# 03_-_MATRIX_SCHEMATIC.net
KiCad netlist of a schematic drawn in Altium Designer
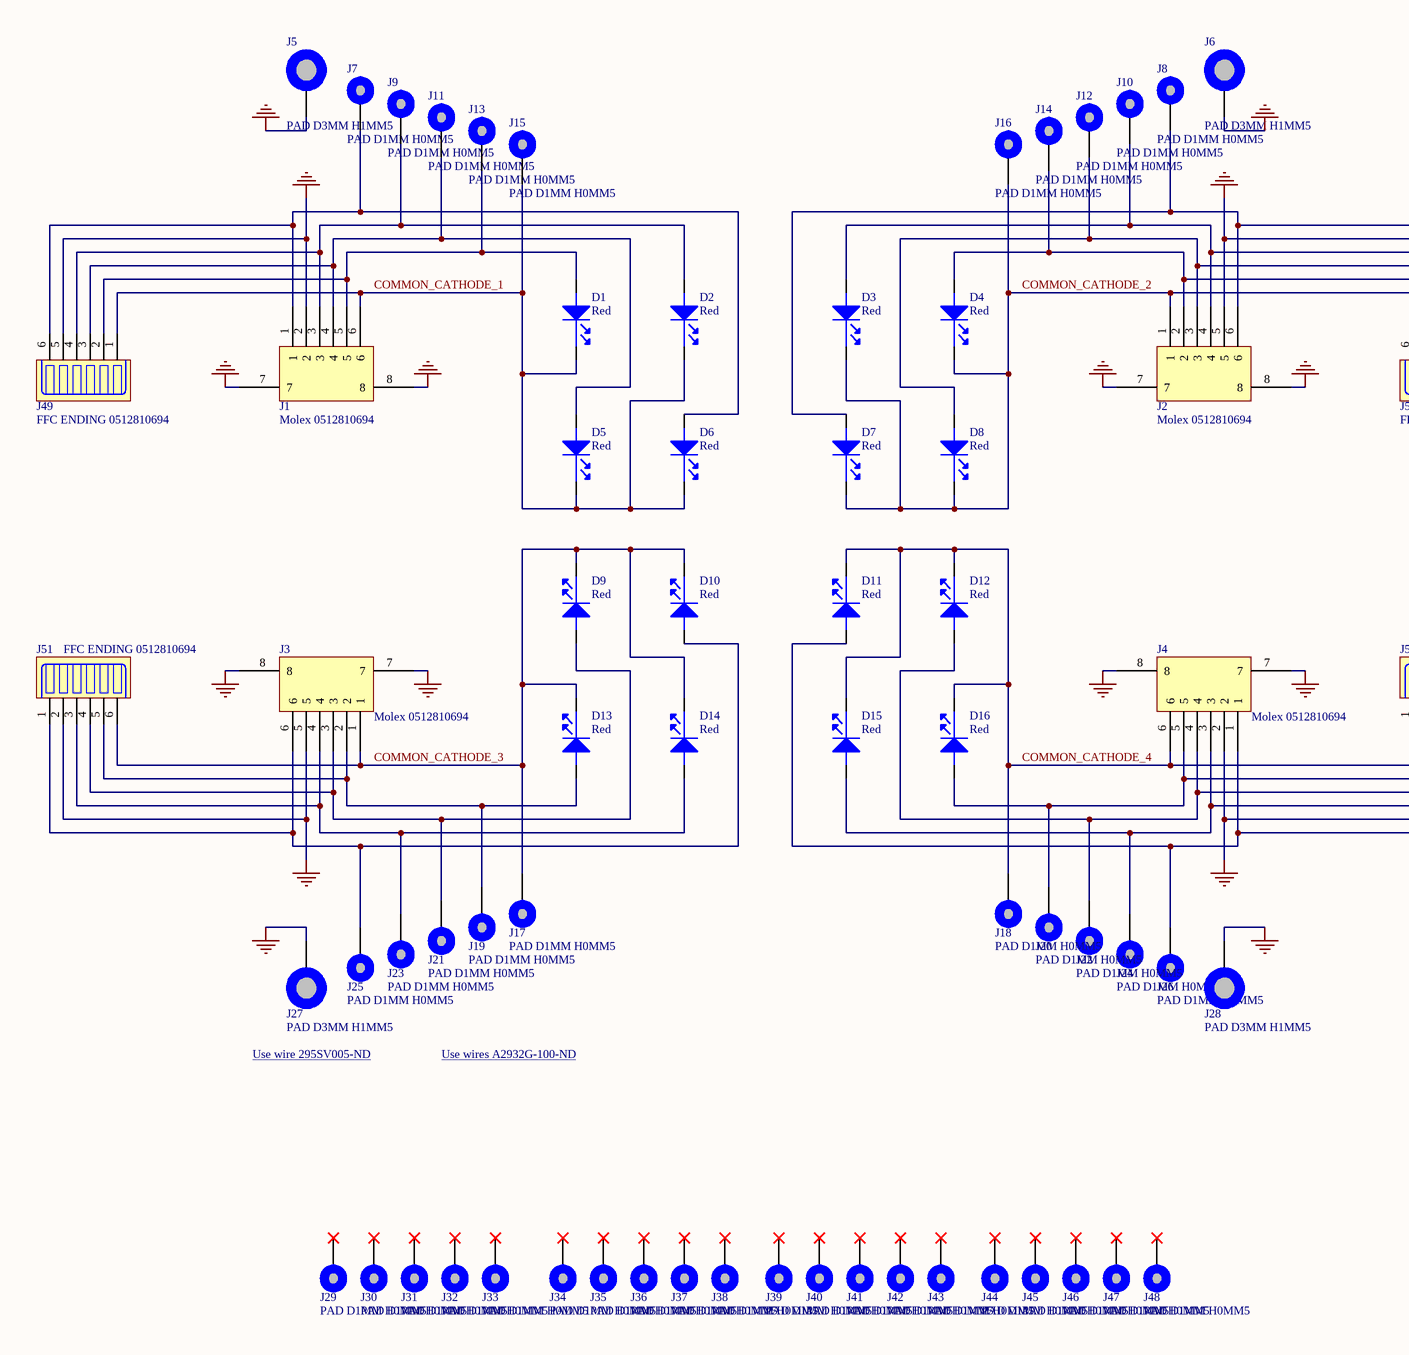
[diagram p0: [03] - MATRIX SCHEMATIC.SchDoc, left]
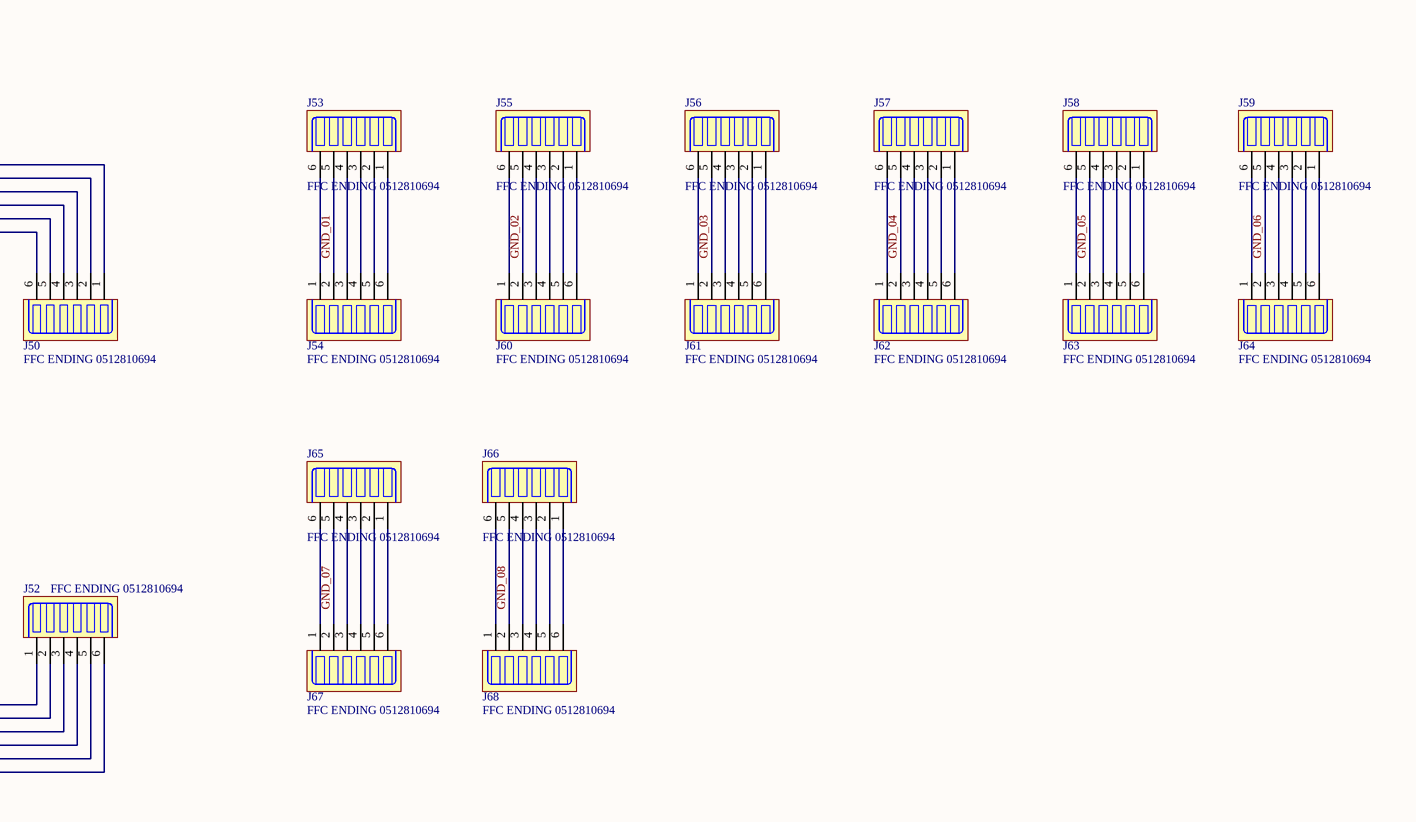
[diagram p1: [03] - MATRIX SCHEMATIC.SchDoc, right]

(export (version "E")
  (design (tool "Eeschema 10.0.6"))
  (components
    (comp (ref "D1")
      (value "Red")
      (footprint "LED_0603")
      (description "LED SMARTLED RED 630NM 0603 SMD")
      (fields
        (field (name "MANUFACTURER") "OSRAM Opto Semiconductors Inc")
        (field (name "MANUFACTURER PART NUMBER") "LS L29K-H1J2-1-Z")
      )
      (libsource (lib "Integrated_Library_FEDEVEL_APR_2015") (part "LS L29K-H1J2-1-Z"))
    )
    (comp (ref "D2")
      (value "Red")
      (footprint "LED_0603")
      (description "LED SMARTLED RED 630NM 0603 SMD")
      (fields
        (field (name "MANUFACTURER") "OSRAM Opto Semiconductors Inc")
        (field (name "MANUFACTURER PART NUMBER") "LS L29K-H1J2-1-Z")
      )
      (libsource (lib "Integrated_Library_FEDEVEL_APR_2015") (part "LS L29K-H1J2-1-Z"))
    )
    (comp (ref "D3")
      (value "Red")
      (footprint "LED_0603")
      (description "LED SMARTLED RED 630NM 0603 SMD")
      (fields
        (field (name "MANUFACTURER") "OSRAM Opto Semiconductors Inc")
        (field (name "MANUFACTURER PART NUMBER") "LS L29K-H1J2-1-Z")
      )
      (libsource (lib "Integrated_Library_FEDEVEL_APR_2015") (part "LS L29K-H1J2-1-Z"))
    )
    (comp (ref "D4")
      (value "Red")
      (footprint "LED_0603")
      (description "LED SMARTLED RED 630NM 0603 SMD")
      (fields
        (field (name "MANUFACTURER") "OSRAM Opto Semiconductors Inc")
        (field (name "MANUFACTURER PART NUMBER") "LS L29K-H1J2-1-Z")
      )
      (libsource (lib "Integrated_Library_FEDEVEL_APR_2015") (part "LS L29K-H1J2-1-Z"))
    )
    (comp (ref "D5")
      (value "Red")
      (footprint "LED_0603")
      (description "LED SMARTLED RED 630NM 0603 SMD")
      (fields
        (field (name "MANUFACTURER") "OSRAM Opto Semiconductors Inc")
        (field (name "MANUFACTURER PART NUMBER") "LS L29K-H1J2-1-Z")
      )
      (libsource (lib "Integrated_Library_FEDEVEL_APR_2015") (part "LS L29K-H1J2-1-Z"))
    )
    (comp (ref "D6")
      (value "Red")
      (footprint "LED_0603")
      (description "LED SMARTLED RED 630NM 0603 SMD")
      (fields
        (field (name "MANUFACTURER") "OSRAM Opto Semiconductors Inc")
        (field (name "MANUFACTURER PART NUMBER") "LS L29K-H1J2-1-Z")
      )
      (libsource (lib "Integrated_Library_FEDEVEL_APR_2015") (part "LS L29K-H1J2-1-Z"))
    )
    (comp (ref "D7")
      (value "Red")
      (footprint "LED_0603")
      (description "LED SMARTLED RED 630NM 0603 SMD")
      (fields
        (field (name "MANUFACTURER") "OSRAM Opto Semiconductors Inc")
        (field (name "MANUFACTURER PART NUMBER") "LS L29K-H1J2-1-Z")
      )
      (libsource (lib "Integrated_Library_FEDEVEL_APR_2015") (part "LS L29K-H1J2-1-Z"))
    )
    (comp (ref "D8")
      (value "Red")
      (footprint "LED_0603")
      (description "LED SMARTLED RED 630NM 0603 SMD")
      (fields
        (field (name "MANUFACTURER") "OSRAM Opto Semiconductors Inc")
        (field (name "MANUFACTURER PART NUMBER") "LS L29K-H1J2-1-Z")
      )
      (libsource (lib "Integrated_Library_FEDEVEL_APR_2015") (part "LS L29K-H1J2-1-Z"))
    )
    (comp (ref "D9")
      (value "Red")
      (footprint "LED_0603")
      (description "LED SMARTLED RED 630NM 0603 SMD")
      (fields
        (field (name "MANUFACTURER") "OSRAM Opto Semiconductors Inc")
        (field (name "MANUFACTURER PART NUMBER") "LS L29K-H1J2-1-Z")
      )
      (libsource (lib "Integrated_Library_FEDEVEL_APR_2015") (part "LS L29K-H1J2-1-Z"))
    )
    (comp (ref "D10")
      (value "Red")
      (footprint "LED_0603")
      (description "LED SMARTLED RED 630NM 0603 SMD")
      (fields
        (field (name "MANUFACTURER") "OSRAM Opto Semiconductors Inc")
        (field (name "MANUFACTURER PART NUMBER") "LS L29K-H1J2-1-Z")
      )
      (libsource (lib "Integrated_Library_FEDEVEL_APR_2015") (part "LS L29K-H1J2-1-Z"))
    )
    (comp (ref "D11")
      (value "Red")
      (footprint "LED_0603")
      (description "LED SMARTLED RED 630NM 0603 SMD")
      (fields
        (field (name "MANUFACTURER") "OSRAM Opto Semiconductors Inc")
        (field (name "MANUFACTURER PART NUMBER") "LS L29K-H1J2-1-Z")
      )
      (libsource (lib "Integrated_Library_FEDEVEL_APR_2015") (part "LS L29K-H1J2-1-Z"))
    )
    (comp (ref "D12")
      (value "Red")
      (footprint "LED_0603")
      (description "LED SMARTLED RED 630NM 0603 SMD")
      (fields
        (field (name "MANUFACTURER") "OSRAM Opto Semiconductors Inc")
        (field (name "MANUFACTURER PART NUMBER") "LS L29K-H1J2-1-Z")
      )
      (libsource (lib "Integrated_Library_FEDEVEL_APR_2015") (part "LS L29K-H1J2-1-Z"))
    )
    (comp (ref "D13")
      (value "Red")
      (footprint "LED_0603")
      (description "LED SMARTLED RED 630NM 0603 SMD")
      (fields
        (field (name "MANUFACTURER") "OSRAM Opto Semiconductors Inc")
        (field (name "MANUFACTURER PART NUMBER") "LS L29K-H1J2-1-Z")
      )
      (libsource (lib "Integrated_Library_FEDEVEL_APR_2015") (part "LS L29K-H1J2-1-Z"))
    )
    (comp (ref "D14")
      (value "Red")
      (footprint "LED_0603")
      (description "LED SMARTLED RED 630NM 0603 SMD")
      (fields
        (field (name "MANUFACTURER") "OSRAM Opto Semiconductors Inc")
        (field (name "MANUFACTURER PART NUMBER") "LS L29K-H1J2-1-Z")
      )
      (libsource (lib "Integrated_Library_FEDEVEL_APR_2015") (part "LS L29K-H1J2-1-Z"))
    )
    (comp (ref "D15")
      (value "Red")
      (footprint "LED_0603")
      (description "LED SMARTLED RED 630NM 0603 SMD")
      (fields
        (field (name "MANUFACTURER") "OSRAM Opto Semiconductors Inc")
        (field (name "MANUFACTURER PART NUMBER") "LS L29K-H1J2-1-Z")
      )
      (libsource (lib "Integrated_Library_FEDEVEL_APR_2015") (part "LS L29K-H1J2-1-Z"))
    )
    (comp (ref "D16")
      (value "Red")
      (footprint "LED_0603")
      (description "LED SMARTLED RED 630NM 0603 SMD")
      (fields
        (field (name "MANUFACTURER") "OSRAM Opto Semiconductors Inc")
        (field (name "MANUFACTURER PART NUMBER") "LS L29K-H1J2-1-Z")
      )
      (libsource (lib "Integrated_Library_FEDEVEL_APR_2015") (part "LS L29K-H1J2-1-Z"))
    )
    (comp (ref "J1")
      (value "Molex 0512810694")
      (footprint "0512810694")
      (description "Conn FPC Connector SKT 6 POS 0.5mm Solder RA SMD Easy-On™ Embossed T/R")
      (fields
        (field (name "MANUFACTURER") "Molex")
        (field (name "MANUFACTURER PART NUMBER") "0512810694")
        (field (name ".CREATOR") "RF")
      )
      (libsource (lib "") (part "0512810694_1"))
    )
    (comp (ref "J2")
      (value "Molex 0512810694")
      (footprint "0512810694")
      (description "Conn FPC Connector SKT 6 POS 0.5mm Solder RA SMD Easy-On™ Embossed T/R")
      (fields
        (field (name "MANUFACTURER") "Molex")
        (field (name "MANUFACTURER PART NUMBER") "0512810694")
        (field (name ".CREATOR") "RF")
      )
      (libsource (lib "") (part "0512810694_1"))
    )
    (comp (ref "J3")
      (value "Molex 0512810694")
      (footprint "0512810694")
      (description "Conn FPC Connector SKT 6 POS 0.5mm Solder RA SMD Easy-On™ Embossed T/R")
      (fields
        (field (name "MANUFACTURER") "Molex")
        (field (name "MANUFACTURER PART NUMBER") "0512810694")
        (field (name ".CREATOR") "RF")
      )
      (libsource (lib "FlexCube_Matrix_4x4 Schlib") (part "0512810694"))
    )
    (comp (ref "J4")
      (value "Molex 0512810694")
      (footprint "0512810694")
      (description "Conn FPC Connector SKT 6 POS 0.5mm Solder RA SMD Easy-On™ Embossed T/R")
      (fields
        (field (name "MANUFACTURER") "Molex")
        (field (name "MANUFACTURER PART NUMBER") "0512810694")
        (field (name ".CREATOR") "RF")
      )
      (libsource (lib "FlexCube_Matrix_4x4 Schlib") (part "0512810694"))
    )
    (comp (ref "J5")
      (value "PAD D3MM H1MM5")
      (footprint "PAD_D3MM_H1MM5")
      (libsource (lib "FlexCube_Matrix_4x4 Schlib") (part "PAD D3MM H1MM5"))
    )
    (comp (ref "J6")
      (value "PAD D3MM H1MM5")
      (footprint "PAD_D3MM_H1MM5")
      (libsource (lib "FlexCube_Matrix_4x4 Schlib") (part "PAD D3MM H1MM5"))
    )
    (comp (ref "J7")
      (value "PAD D1MM H0MM5")
      (footprint "PAD_D1MM_H0MM5")
      (libsource (lib "FlexCube_Matrix_4x4 Schlib") (part "PAD D1MM H0MM5"))
    )
    (comp (ref "J8")
      (value "PAD D1MM H0MM5")
      (footprint "PAD_D1MM_H0MM5")
      (libsource (lib "FlexCube_Matrix_4x4 Schlib") (part "PAD D1MM H0MM5"))
    )
    (comp (ref "J9")
      (value "PAD D1MM H0MM5")
      (footprint "PAD_D1MM_H0MM5")
      (libsource (lib "FlexCube_Matrix_4x4 Schlib") (part "PAD D1MM H0MM5"))
    )
    (comp (ref "J10")
      (value "PAD D1MM H0MM5")
      (footprint "PAD_D1MM_H0MM5")
      (libsource (lib "FlexCube_Matrix_4x4 Schlib") (part "PAD D1MM H0MM5"))
    )
    (comp (ref "J11")
      (value "PAD D1MM H0MM5")
      (footprint "PAD_D1MM_H0MM5")
      (libsource (lib "FlexCube_Matrix_4x4 Schlib") (part "PAD D1MM H0MM5"))
    )
    (comp (ref "J12")
      (value "PAD D1MM H0MM5")
      (footprint "PAD_D1MM_H0MM5")
      (libsource (lib "FlexCube_Matrix_4x4 Schlib") (part "PAD D1MM H0MM5"))
    )
    (comp (ref "J13")
      (value "PAD D1MM H0MM5")
      (footprint "PAD_D1MM_H0MM5")
      (libsource (lib "FlexCube_Matrix_4x4 Schlib") (part "PAD D1MM H0MM5"))
    )
    (comp (ref "J14")
      (value "PAD D1MM H0MM5")
      (footprint "PAD_D1MM_H0MM5")
      (libsource (lib "FlexCube_Matrix_4x4 Schlib") (part "PAD D1MM H0MM5"))
    )
    (comp (ref "J15")
      (value "PAD D1MM H0MM5")
      (footprint "PAD_D1MM_H0MM5")
      (libsource (lib "FlexCube_Matrix_4x4 Schlib") (part "PAD D1MM H0MM5"))
    )
    (comp (ref "J16")
      (value "PAD D1MM H0MM5")
      (footprint "PAD_D1MM_H0MM5")
      (libsource (lib "FlexCube_Matrix_4x4 Schlib") (part "PAD D1MM H0MM5"))
    )
    (comp (ref "J17")
      (value "PAD D1MM H0MM5")
      (footprint "PAD_D1MM_H0MM5")
      (libsource (lib "FlexCube_Matrix_4x4 Schlib") (part "PAD D1MM H0MM5"))
    )
    (comp (ref "J18")
      (value "PAD D1MM H0MM5")
      (footprint "PAD_D1MM_H0MM5")
      (libsource (lib "FlexCube_Matrix_4x4 Schlib") (part "PAD D1MM H0MM5"))
    )
    (comp (ref "J19")
      (value "PAD D1MM H0MM5")
      (footprint "PAD_D1MM_H0MM5")
      (libsource (lib "FlexCube_Matrix_4x4 Schlib") (part "PAD D1MM H0MM5"))
    )
    (comp (ref "J20")
      (value "PAD D1MM H0MM5")
      (footprint "PAD_D1MM_H0MM5")
      (libsource (lib "FlexCube_Matrix_4x4 Schlib") (part "PAD D1MM H0MM5"))
    )
    (comp (ref "J21")
      (value "PAD D1MM H0MM5")
      (footprint "PAD_D1MM_H0MM5")
      (libsource (lib "FlexCube_Matrix_4x4 Schlib") (part "PAD D1MM H0MM5"))
    )
    (comp (ref "J22")
      (value "PAD D1MM H0MM5")
      (footprint "PAD_D1MM_H0MM5")
      (libsource (lib "FlexCube_Matrix_4x4 Schlib") (part "PAD D1MM H0MM5"))
    )
    (comp (ref "J23")
      (value "PAD D1MM H0MM5")
      (footprint "PAD_D1MM_H0MM5")
      (libsource (lib "FlexCube_Matrix_4x4 Schlib") (part "PAD D1MM H0MM5"))
    )
    (comp (ref "J24")
      (value "PAD D1MM H0MM5")
      (footprint "PAD_D1MM_H0MM5")
      (libsource (lib "FlexCube_Matrix_4x4 Schlib") (part "PAD D1MM H0MM5"))
    )
    (comp (ref "J25")
      (value "PAD D1MM H0MM5")
      (footprint "PAD_D1MM_H0MM5")
      (libsource (lib "FlexCube_Matrix_4x4 Schlib") (part "PAD D1MM H0MM5"))
    )
    (comp (ref "J26")
      (value "PAD D1MM H0MM5")
      (footprint "PAD_D1MM_H0MM5")
      (libsource (lib "FlexCube_Matrix_4x4 Schlib") (part "PAD D1MM H0MM5"))
    )
    (comp (ref "J27")
      (value "PAD D3MM H1MM5")
      (footprint "PAD_D3MM_H1MM5")
      (libsource (lib "FlexCube_Matrix_4x4 Schlib") (part "PAD D3MM H1MM5"))
    )
    (comp (ref "J28")
      (value "PAD D3MM H1MM5")
      (footprint "PAD_D3MM_H1MM5")
      (libsource (lib "FlexCube_Matrix_4x4 Schlib") (part "PAD D3MM H1MM5"))
    )
    (comp (ref "J29")
      (value "PAD D1MM H0MM5")
      (footprint "PAD_D1MM_H0MM5")
      (libsource (lib "FlexCube_Matrix_4x4 Schlib") (part "PAD D1MM H0MM5"))
    )
    (comp (ref "J30")
      (value "PAD D1MM H0MM5")
      (footprint "PAD_D1MM_H0MM5")
      (libsource (lib "FlexCube_Matrix_4x4 Schlib") (part "PAD D1MM H0MM5"))
    )
    (comp (ref "J31")
      (value "PAD D1MM H0MM5")
      (footprint "PAD_D1MM_H0MM5")
      (libsource (lib "FlexCube_Matrix_4x4 Schlib") (part "PAD D1MM H0MM5"))
    )
    (comp (ref "J32")
      (value "PAD D1MM H0MM5")
      (footprint "PAD_D1MM_H0MM5")
      (libsource (lib "FlexCube_Matrix_4x4 Schlib") (part "PAD D1MM H0MM5"))
    )
    (comp (ref "J33")
      (value "PAD D1MM H0MM5")
      (footprint "PAD_D1MM_H0MM5")
      (libsource (lib "FlexCube_Matrix_4x4 Schlib") (part "PAD D1MM H0MM5"))
    )
    (comp (ref "J34")
      (value "PAD D1MM H0MM5")
      (footprint "PAD_D1MM_H0MM5")
      (libsource (lib "FlexCube_Matrix_4x4 Schlib") (part "PAD D1MM H0MM5"))
    )
    (comp (ref "J35")
      (value "PAD D1MM H0MM5")
      (footprint "PAD_D1MM_H0MM5")
      (libsource (lib "FlexCube_Matrix_4x4 Schlib") (part "PAD D1MM H0MM5"))
    )
    (comp (ref "J36")
      (value "PAD D1MM H0MM5")
      (footprint "PAD_D1MM_H0MM5")
      (libsource (lib "FlexCube_Matrix_4x4 Schlib") (part "PAD D1MM H0MM5"))
    )
    (comp (ref "J37")
      (value "PAD D1MM H0MM5")
      (footprint "PAD_D1MM_H0MM5")
      (libsource (lib "FlexCube_Matrix_4x4 Schlib") (part "PAD D1MM H0MM5"))
    )
    (comp (ref "J38")
      (value "PAD D1MM H0MM5")
      (footprint "PAD_D1MM_H0MM5")
      (libsource (lib "FlexCube_Matrix_4x4 Schlib") (part "PAD D1MM H0MM5"))
    )
    (comp (ref "J39")
      (value "PAD D1MM H0MM5")
      (footprint "PAD_D1MM_H0MM5")
      (libsource (lib "FlexCube_Matrix_4x4 Schlib") (part "PAD D1MM H0MM5"))
    )
    (comp (ref "J40")
      (value "PAD D1MM H0MM5")
      (footprint "PAD_D1MM_H0MM5")
      (libsource (lib "FlexCube_Matrix_4x4 Schlib") (part "PAD D1MM H0MM5"))
    )
    (comp (ref "J41")
      (value "PAD D1MM H0MM5")
      (footprint "PAD_D1MM_H0MM5")
      (libsource (lib "FlexCube_Matrix_4x4 Schlib") (part "PAD D1MM H0MM5"))
    )
    (comp (ref "J42")
      (value "PAD D1MM H0MM5")
      (footprint "PAD_D1MM_H0MM5")
      (libsource (lib "FlexCube_Matrix_4x4 Schlib") (part "PAD D1MM H0MM5"))
    )
    (comp (ref "J43")
      (value "PAD D1MM H0MM5")
      (footprint "PAD_D1MM_H0MM5")
      (libsource (lib "FlexCube_Matrix_4x4 Schlib") (part "PAD D1MM H0MM5"))
    )
    (comp (ref "J44")
      (value "PAD D1MM H0MM5")
      (footprint "PAD_D1MM_H0MM5")
      (libsource (lib "FlexCube_Matrix_4x4 Schlib") (part "PAD D1MM H0MM5"))
    )
    (comp (ref "J45")
      (value "PAD D1MM H0MM5")
      (footprint "PAD_D1MM_H0MM5")
      (libsource (lib "FlexCube_Matrix_4x4 Schlib") (part "PAD D1MM H0MM5"))
    )
    (comp (ref "J46")
      (value "PAD D1MM H0MM5")
      (footprint "PAD_D1MM_H0MM5")
      (libsource (lib "FlexCube_Matrix_4x4 Schlib") (part "PAD D1MM H0MM5"))
    )
    (comp (ref "J47")
      (value "PAD D1MM H0MM5")
      (footprint "PAD_D1MM_H0MM5")
      (libsource (lib "FlexCube_Matrix_4x4 Schlib") (part "PAD D1MM H0MM5"))
    )
    (comp (ref "J48")
      (value "PAD D1MM H0MM5")
      (footprint "PAD_D1MM_H0MM5")
      (libsource (lib "FlexCube_Matrix_4x4 Schlib") (part "PAD D1MM H0MM5"))
    )
    (comp (ref "J49")
      (value "FFC ENDING 0512810694")
      (footprint "FFC_ENDING_0512810694")
      (libsource (lib "") (part "FFC ENDING 0512810694_3"))
    )
    (comp (ref "J50")
      (value "FFC ENDING 0512810694")
      (footprint "FFC_ENDING_0512810694")
      (libsource (lib "") (part "FFC ENDING 0512810694_3"))
    )
    (comp (ref "J51")
      (value "FFC ENDING 0512810694")
      (footprint "FFC_ENDING_0512810694")
      (libsource (lib "FlexCube_Matrix_4x4 Schlib") (part "FFC ENDING 0512810694"))
    )
    (comp (ref "J52")
      (value "FFC ENDING 0512810694")
      (footprint "FFC_ENDING_0512810694")
      (libsource (lib "FlexCube_Matrix_4x4 Schlib") (part "FFC ENDING 0512810694"))
    )
    (comp (ref "J53")
      (value "FFC ENDING 0512810694")
      (footprint "FFC_ENDING_0512810694")
      (libsource (lib "") (part "FFC ENDING 0512810694_1"))
    )
    (comp (ref "J54")
      (value "FFC ENDING 0512810694")
      (footprint "FFC_ENDING_0512810694")
      (libsource (lib "") (part "FFC ENDING 0512810694_2"))
    )
    (comp (ref "J55")
      (value "FFC ENDING 0512810694")
      (footprint "FFC_ENDING_0512810694")
      (libsource (lib "") (part "FFC ENDING 0512810694_1"))
    )
    (comp (ref "J56")
      (value "FFC ENDING 0512810694")
      (footprint "FFC_ENDING_0512810694")
      (libsource (lib "") (part "FFC ENDING 0512810694_1"))
    )
    (comp (ref "J57")
      (value "FFC ENDING 0512810694")
      (footprint "FFC_ENDING_0512810694")
      (libsource (lib "") (part "FFC ENDING 0512810694_1"))
    )
    (comp (ref "J58")
      (value "FFC ENDING 0512810694")
      (footprint "FFC_ENDING_0512810694")
      (libsource (lib "") (part "FFC ENDING 0512810694_1"))
    )
    (comp (ref "J59")
      (value "FFC ENDING 0512810694")
      (footprint "FFC_ENDING_0512810694")
      (libsource (lib "") (part "FFC ENDING 0512810694_1"))
    )
    (comp (ref "J60")
      (value "FFC ENDING 0512810694")
      (footprint "FFC_ENDING_0512810694")
      (libsource (lib "") (part "FFC ENDING 0512810694_2"))
    )
    (comp (ref "J61")
      (value "FFC ENDING 0512810694")
      (footprint "FFC_ENDING_0512810694")
      (libsource (lib "") (part "FFC ENDING 0512810694_2"))
    )
    (comp (ref "J62")
      (value "FFC ENDING 0512810694")
      (footprint "FFC_ENDING_0512810694")
      (libsource (lib "") (part "FFC ENDING 0512810694_2"))
    )
    (comp (ref "J63")
      (value "FFC ENDING 0512810694")
      (footprint "FFC_ENDING_0512810694")
      (libsource (lib "") (part "FFC ENDING 0512810694_2"))
    )
    (comp (ref "J64")
      (value "FFC ENDING 0512810694")
      (footprint "FFC_ENDING_0512810694")
      (libsource (lib "") (part "FFC ENDING 0512810694_2"))
    )
    (comp (ref "J65")
      (value "FFC ENDING 0512810694")
      (footprint "FFC_ENDING_0512810694")
      (libsource (lib "") (part "FFC ENDING 0512810694_1"))
    )
    (comp (ref "J66")
      (value "FFC ENDING 0512810694")
      (footprint "FFC_ENDING_0512810694")
      (libsource (lib "") (part "FFC ENDING 0512810694_1"))
    )
    (comp (ref "J67")
      (value "FFC ENDING 0512810694")
      (footprint "FFC_ENDING_0512810694")
      (libsource (lib "") (part "FFC ENDING 0512810694_2"))
    )
    (comp (ref "J68")
      (value "FFC ENDING 0512810694")
      (footprint "FFC_ENDING_0512810694")
      (libsource (lib "") (part "FFC ENDING 0512810694_2"))
    )
  )
  (nets
    (net (code "1") (name "/COMMON_CATHODE_1") (class "Default")
      (node (ref "D1") (pin "1") (pinfunction "cathode_1") (pintype "passive"))
      (node (ref "D2") (pin "1") (pinfunction "cathode_1") (pintype "passive"))
      (node (ref "D5") (pin "1") (pinfunction "cathode_1") (pintype "passive"))
      (node (ref "D6") (pin "1") (pinfunction "cathode_1") (pintype "passive"))
      (node (ref "J1") (pin "6") (pinfunction "6_6") (pintype "passive"))
      (node (ref "J15") (pin "1") (pinfunction "1_1") (pintype "passive"))
      (node (ref "J49") (pin "1") (pinfunction "1_1") (pintype "passive"))
    )
    (net (code "2") (name "/COMMON_CATHODE_2") (class "Default")
      (node (ref "D3") (pin "1") (pinfunction "cathode_1") (pintype "passive"))
      (node (ref "D4") (pin "1") (pinfunction "cathode_1") (pintype "passive"))
      (node (ref "D7") (pin "1") (pinfunction "cathode_1") (pintype "passive"))
      (node (ref "D8") (pin "1") (pinfunction "cathode_1") (pintype "passive"))
      (node (ref "J16") (pin "1") (pinfunction "1_1") (pintype "passive"))
      (node (ref "J2") (pin "1") (pinfunction "1_1") (pintype "passive"))
      (node (ref "J50") (pin "6") (pinfunction "6_6") (pintype "passive"))
    )
    (net (code "3") (name "/COMMON_CATHODE_3") (class "Default")
      (node (ref "D10") (pin "1") (pinfunction "cathode_1") (pintype "passive"))
      (node (ref "D13") (pin "1") (pinfunction "cathode_1") (pintype "passive"))
      (node (ref "D14") (pin "1") (pinfunction "cathode_1") (pintype "passive"))
      (node (ref "D9") (pin "1") (pinfunction "cathode_1") (pintype "passive"))
      (node (ref "J17") (pin "1") (pinfunction "1_1") (pintype "passive"))
      (node (ref "J3") (pin "1") (pinfunction "1_1") (pintype "passive"))
      (node (ref "J51") (pin "6") (pinfunction "6_6") (pintype "passive"))
    )
    (net (code "4") (name "/COMMON_CATHODE_4") (class "Default")
      (node (ref "D11") (pin "1") (pinfunction "cathode_1") (pintype "passive"))
      (node (ref "D12") (pin "1") (pinfunction "cathode_1") (pintype "passive"))
      (node (ref "D15") (pin "1") (pinfunction "cathode_1") (pintype "passive"))
      (node (ref "D16") (pin "1") (pinfunction "cathode_1") (pintype "passive"))
      (node (ref "J18") (pin "1") (pinfunction "1_1") (pintype "passive"))
      (node (ref "J4") (pin "6") (pinfunction "6_6") (pintype "passive"))
      (node (ref "J52") (pin "1") (pinfunction "1_1") (pintype "passive"))
    )
    (net (code "5") (name "/GND_01") (class "Default")
      (node (ref "J53") (pin "5") (pinfunction "5_5") (pintype "passive"))
      (node (ref "J54") (pin "2") (pinfunction "2_2") (pintype "passive"))
    )
    (net (code "6") (name "/GND_02") (class "Default")
      (node (ref "J55") (pin "5") (pinfunction "5_5") (pintype "passive"))
      (node (ref "J60") (pin "2") (pinfunction "2_2") (pintype "passive"))
    )
    (net (code "7") (name "/GND_03") (class "Default")
      (node (ref "J56") (pin "5") (pinfunction "5_5") (pintype "passive"))
      (node (ref "J61") (pin "2") (pinfunction "2_2") (pintype "passive"))
    )
    (net (code "8") (name "/GND_04") (class "Default")
      (node (ref "J57") (pin "5") (pinfunction "5_5") (pintype "passive"))
      (node (ref "J62") (pin "2") (pinfunction "2_2") (pintype "passive"))
    )
    (net (code "9") (name "/GND_05") (class "Default")
      (node (ref "J58") (pin "5") (pinfunction "5_5") (pintype "passive"))
      (node (ref "J63") (pin "2") (pinfunction "2_2") (pintype "passive"))
    )
    (net (code "10") (name "/GND_06") (class "Default")
      (node (ref "J59") (pin "5") (pinfunction "5_5") (pintype "passive"))
      (node (ref "J64") (pin "2") (pinfunction "2_2") (pintype "passive"))
    )
    (net (code "11") (name "/GND_07") (class "Default")
      (node (ref "J65") (pin "5") (pinfunction "5_5") (pintype "passive"))
      (node (ref "J67") (pin "2") (pinfunction "2_2") (pintype "passive"))
    )
    (net (code "12") (name "/GND_08") (class "Default")
      (node (ref "J66") (pin "5") (pinfunction "5_5") (pintype "passive"))
      (node (ref "J68") (pin "2") (pinfunction "2_2") (pintype "passive"))
    )
    (net (code "13") (name "GND") (class "Default")
      (node (ref "J1") (pin "2") (pinfunction "2_2") (pintype "passive"))
      (node (ref "J1") (pin "7") (pinfunction "7_7") (pintype "passive"))
      (node (ref "J1") (pin "8") (pinfunction "8_8") (pintype "passive"))
      (node (ref "J2") (pin "5") (pinfunction "5_5") (pintype "passive"))
      (node (ref "J2") (pin "7") (pinfunction "7_7") (pintype "passive"))
      (node (ref "J2") (pin "8") (pinfunction "8_8") (pintype "passive"))
      (node (ref "J27") (pin "1") (pinfunction "1_1") (pintype "passive"))
      (node (ref "J28") (pin "1") (pinfunction "1_1") (pintype "passive"))
      (node (ref "J3") (pin "5") (pinfunction "5_5") (pintype "passive"))
      (node (ref "J3") (pin "7") (pinfunction "7_7") (pintype "passive"))
      (node (ref "J3") (pin "8") (pinfunction "8_8") (pintype "passive"))
      (node (ref "J4") (pin "2") (pinfunction "2_2") (pintype "passive"))
      (node (ref "J4") (pin "7") (pinfunction "7_7") (pintype "passive"))
      (node (ref "J4") (pin "8") (pinfunction "8_8") (pintype "passive"))
      (node (ref "J49") (pin "5") (pinfunction "5_5") (pintype "passive"))
      (node (ref "J5") (pin "1") (pinfunction "1_1") (pintype "passive"))
      (node (ref "J50") (pin "2") (pinfunction "2_2") (pintype "passive"))
      (node (ref "J51") (pin "2") (pinfunction "2_2") (pintype "passive"))
      (node (ref "J52") (pin "5") (pinfunction "5_5") (pintype "passive"))
      (node (ref "J6") (pin "1") (pinfunction "1_1") (pintype "passive"))
    )
    (net (code "14") (name "Net-(D1-ANODE)") (class "Default")
      (node (ref "D1") (pin "2") (pinfunction "ANODE_2") (pintype "passive"))
      (node (ref "J1") (pin "5") (pinfunction "5_5") (pintype "passive"))
      (node (ref "J13") (pin "1") (pinfunction "1_1") (pintype "passive"))
      (node (ref "J49") (pin "2") (pinfunction "2_2") (pintype "passive"))
    )
    (net (code "15") (name "Net-(D2-ANODE)") (class "Default")
      (node (ref "D2") (pin "2") (pinfunction "ANODE_2") (pintype "passive"))
      (node (ref "J1") (pin "3") (pinfunction "3_3") (pintype "passive"))
      (node (ref "J49") (pin "4") (pinfunction "4_4") (pintype "passive"))
      (node (ref "J9") (pin "1") (pinfunction "1_1") (pintype "passive"))
    )
    (net (code "16") (name "Net-(D3-ANODE)") (class "Default")
      (node (ref "D3") (pin "2") (pinfunction "ANODE_2") (pintype "passive"))
      (node (ref "J10") (pin "1") (pinfunction "1_1") (pintype "passive"))
      (node (ref "J2") (pin "4") (pinfunction "4_4") (pintype "passive"))
      (node (ref "J50") (pin "3") (pinfunction "3_3") (pintype "passive"))
    )
    (net (code "17") (name "Net-(D4-ANODE)") (class "Default")
      (node (ref "D4") (pin "2") (pinfunction "ANODE_2") (pintype "passive"))
      (node (ref "J14") (pin "1") (pinfunction "1_1") (pintype "passive"))
      (node (ref "J2") (pin "2") (pinfunction "2_2") (pintype "passive"))
      (node (ref "J50") (pin "5") (pinfunction "5_5") (pintype "passive"))
    )
    (net (code "18") (name "Net-(D5-ANODE)") (class "Default")
      (node (ref "D5") (pin "2") (pinfunction "ANODE_2") (pintype "passive"))
      (node (ref "J1") (pin "4") (pinfunction "4_4") (pintype "passive"))
      (node (ref "J11") (pin "1") (pinfunction "1_1") (pintype "passive"))
      (node (ref "J49") (pin "3") (pinfunction "3_3") (pintype "passive"))
    )
    (net (code "19") (name "Net-(D6-ANODE)") (class "Default")
      (node (ref "D6") (pin "2") (pinfunction "ANODE_2") (pintype "passive"))
      (node (ref "J1") (pin "1") (pinfunction "1_1") (pintype "passive"))
      (node (ref "J49") (pin "6") (pinfunction "6_6") (pintype "passive"))
      (node (ref "J7") (pin "1") (pinfunction "1_1") (pintype "passive"))
    )
    (net (code "20") (name "Net-(D7-ANODE)") (class "Default")
      (node (ref "D7") (pin "2") (pinfunction "ANODE_2") (pintype "passive"))
      (node (ref "J2") (pin "6") (pinfunction "6_6") (pintype "passive"))
      (node (ref "J50") (pin "1") (pinfunction "1_1") (pintype "passive"))
      (node (ref "J8") (pin "1") (pinfunction "1_1") (pintype "passive"))
    )
    (net (code "21") (name "Net-(D8-ANODE)") (class "Default")
      (node (ref "D8") (pin "2") (pinfunction "ANODE_2") (pintype "passive"))
      (node (ref "J12") (pin "1") (pinfunction "1_1") (pintype "passive"))
      (node (ref "J2") (pin "3") (pinfunction "3_3") (pintype "passive"))
      (node (ref "J50") (pin "4") (pinfunction "4_4") (pintype "passive"))
    )
    (net (code "22") (name "Net-(D9-ANODE)") (class "Default")
      (node (ref "D9") (pin "2") (pinfunction "ANODE_2") (pintype "passive"))
      (node (ref "J21") (pin "1") (pinfunction "1_1") (pintype "passive"))
      (node (ref "J3") (pin "3") (pinfunction "3_3") (pintype "passive"))
      (node (ref "J51") (pin "4") (pinfunction "4_4") (pintype "passive"))
    )
    (net (code "23") (name "Net-(D10-ANODE)") (class "Default")
      (node (ref "D10") (pin "2") (pinfunction "ANODE_2") (pintype "passive"))
      (node (ref "J25") (pin "1") (pinfunction "1_1") (pintype "passive"))
      (node (ref "J3") (pin "6") (pinfunction "6_6") (pintype "passive"))
      (node (ref "J51") (pin "1") (pinfunction "1_1") (pintype "passive"))
    )
    (net (code "24") (name "Net-(D11-ANODE)") (class "Default")
      (node (ref "D11") (pin "2") (pinfunction "ANODE_2") (pintype "passive"))
      (node (ref "J26") (pin "1") (pinfunction "1_1") (pintype "passive"))
      (node (ref "J4") (pin "1") (pinfunction "1_1") (pintype "passive"))
      (node (ref "J52") (pin "6") (pinfunction "6_6") (pintype "passive"))
    )
    (net (code "25") (name "Net-(D12-ANODE)") (class "Default")
      (node (ref "D12") (pin "2") (pinfunction "ANODE_2") (pintype "passive"))
      (node (ref "J22") (pin "1") (pinfunction "1_1") (pintype "passive"))
      (node (ref "J4") (pin "4") (pinfunction "4_4") (pintype "passive"))
      (node (ref "J52") (pin "3") (pinfunction "3_3") (pintype "passive"))
    )
    (net (code "26") (name "Net-(D13-ANODE)") (class "Default")
      (node (ref "D13") (pin "2") (pinfunction "ANODE_2") (pintype "passive"))
      (node (ref "J19") (pin "1") (pinfunction "1_1") (pintype "passive"))
      (node (ref "J3") (pin "2") (pinfunction "2_2") (pintype "passive"))
      (node (ref "J51") (pin "5") (pinfunction "5_5") (pintype "passive"))
    )
    (net (code "27") (name "Net-(D14-ANODE)") (class "Default")
      (node (ref "D14") (pin "2") (pinfunction "ANODE_2") (pintype "passive"))
      (node (ref "J23") (pin "1") (pinfunction "1_1") (pintype "passive"))
      (node (ref "J3") (pin "4") (pinfunction "4_4") (pintype "passive"))
      (node (ref "J51") (pin "3") (pinfunction "3_3") (pintype "passive"))
    )
    (net (code "28") (name "Net-(D15-ANODE)") (class "Default")
      (node (ref "D15") (pin "2") (pinfunction "ANODE_2") (pintype "passive"))
      (node (ref "J24") (pin "1") (pinfunction "1_1") (pintype "passive"))
      (node (ref "J4") (pin "3") (pinfunction "3_3") (pintype "passive"))
      (node (ref "J52") (pin "4") (pinfunction "4_4") (pintype "passive"))
    )
    (net (code "29") (name "Net-(D16-ANODE)") (class "Default")
      (node (ref "D16") (pin "2") (pinfunction "ANODE_2") (pintype "passive"))
      (node (ref "J20") (pin "1") (pinfunction "1_1") (pintype "passive"))
      (node (ref "J4") (pin "5") (pinfunction "5_5") (pintype "passive"))
      (node (ref "J52") (pin "2") (pinfunction "2_2") (pintype "passive"))
    )
    (net (code "30") (name "Net-(J53-Pad1)") (class "Default")
      (node (ref "J53") (pin "1") (pinfunction "1_1") (pintype "passive"))
      (node (ref "J54") (pin "6") (pinfunction "6_6") (pintype "passive"))
    )
    (net (code "31") (name "Net-(J53-Pad2)") (class "Default")
      (node (ref "J53") (pin "2") (pinfunction "2_2") (pintype "passive"))
      (node (ref "J54") (pin "5") (pinfunction "5_5") (pintype "passive"))
    )
    (net (code "32") (name "Net-(J53-Pad3)") (class "Default")
      (node (ref "J53") (pin "3") (pinfunction "3_3") (pintype "passive"))
      (node (ref "J54") (pin "4") (pinfunction "4_4") (pintype "passive"))
    )
    (net (code "33") (name "Net-(J53-Pad4)") (class "Default")
      (node (ref "J53") (pin "4") (pinfunction "4_4") (pintype "passive"))
      (node (ref "J54") (pin "3") (pinfunction "3_3") (pintype "passive"))
    )
    (net (code "34") (name "Net-(J53-Pad6)") (class "Default")
      (node (ref "J53") (pin "6") (pinfunction "6_6") (pintype "passive"))
      (node (ref "J54") (pin "1") (pinfunction "1_1") (pintype "passive"))
    )
    (net (code "35") (name "Net-(J55-Pad1)") (class "Default")
      (node (ref "J55") (pin "1") (pinfunction "1_1") (pintype "passive"))
      (node (ref "J60") (pin "6") (pinfunction "6_6") (pintype "passive"))
    )
    (net (code "36") (name "Net-(J55-Pad2)") (class "Default")
      (node (ref "J55") (pin "2") (pinfunction "2_2") (pintype "passive"))
      (node (ref "J60") (pin "5") (pinfunction "5_5") (pintype "passive"))
    )
    (net (code "37") (name "Net-(J55-Pad3)") (class "Default")
      (node (ref "J55") (pin "3") (pinfunction "3_3") (pintype "passive"))
      (node (ref "J60") (pin "4") (pinfunction "4_4") (pintype "passive"))
    )
    (net (code "38") (name "Net-(J55-Pad4)") (class "Default")
      (node (ref "J55") (pin "4") (pinfunction "4_4") (pintype "passive"))
      (node (ref "J60") (pin "3") (pinfunction "3_3") (pintype "passive"))
    )
    (net (code "39") (name "Net-(J55-Pad6)") (class "Default")
      (node (ref "J55") (pin "6") (pinfunction "6_6") (pintype "passive"))
      (node (ref "J60") (pin "1") (pinfunction "1_1") (pintype "passive"))
    )
    (net (code "40") (name "Net-(J56-Pad1)") (class "Default")
      (node (ref "J56") (pin "1") (pinfunction "1_1") (pintype "passive"))
      (node (ref "J61") (pin "6") (pinfunction "6_6") (pintype "passive"))
    )
    (net (code "41") (name "Net-(J56-Pad2)") (class "Default")
      (node (ref "J56") (pin "2") (pinfunction "2_2") (pintype "passive"))
      (node (ref "J61") (pin "5") (pinfunction "5_5") (pintype "passive"))
    )
    (net (code "42") (name "Net-(J56-Pad3)") (class "Default")
      (node (ref "J56") (pin "3") (pinfunction "3_3") (pintype "passive"))
      (node (ref "J61") (pin "4") (pinfunction "4_4") (pintype "passive"))
    )
    (net (code "43") (name "Net-(J56-Pad4)") (class "Default")
      (node (ref "J56") (pin "4") (pinfunction "4_4") (pintype "passive"))
      (node (ref "J61") (pin "3") (pinfunction "3_3") (pintype "passive"))
    )
    (net (code "44") (name "Net-(J56-Pad6)") (class "Default")
      (node (ref "J56") (pin "6") (pinfunction "6_6") (pintype "passive"))
      (node (ref "J61") (pin "1") (pinfunction "1_1") (pintype "passive"))
    )
    (net (code "45") (name "Net-(J57-Pad1)") (class "Default")
      (node (ref "J57") (pin "1") (pinfunction "1_1") (pintype "passive"))
      (node (ref "J62") (pin "6") (pinfunction "6_6") (pintype "passive"))
    )
    (net (code "46") (name "Net-(J57-Pad2)") (class "Default")
      (node (ref "J57") (pin "2") (pinfunction "2_2") (pintype "passive"))
      (node (ref "J62") (pin "5") (pinfunction "5_5") (pintype "passive"))
    )
    (net (code "47") (name "Net-(J57-Pad3)") (class "Default")
      (node (ref "J57") (pin "3") (pinfunction "3_3") (pintype "passive"))
      (node (ref "J62") (pin "4") (pinfunction "4_4") (pintype "passive"))
    )
    (net (code "48") (name "Net-(J57-Pad4)") (class "Default")
      (node (ref "J57") (pin "4") (pinfunction "4_4") (pintype "passive"))
      (node (ref "J62") (pin "3") (pinfunction "3_3") (pintype "passive"))
    )
    (net (code "49") (name "Net-(J57-Pad6)") (class "Default")
      (node (ref "J57") (pin "6") (pinfunction "6_6") (pintype "passive"))
      (node (ref "J62") (pin "1") (pinfunction "1_1") (pintype "passive"))
    )
    (net (code "50") (name "Net-(J58-Pad1)") (class "Default")
      (node (ref "J58") (pin "1") (pinfunction "1_1") (pintype "passive"))
      (node (ref "J63") (pin "6") (pinfunction "6_6") (pintype "passive"))
    )
    (net (code "51") (name "Net-(J58-Pad2)") (class "Default")
      (node (ref "J58") (pin "2") (pinfunction "2_2") (pintype "passive"))
      (node (ref "J63") (pin "5") (pinfunction "5_5") (pintype "passive"))
    )
    (net (code "52") (name "Net-(J58-Pad3)") (class "Default")
      (node (ref "J58") (pin "3") (pinfunction "3_3") (pintype "passive"))
      (node (ref "J63") (pin "4") (pinfunction "4_4") (pintype "passive"))
    )
    (net (code "53") (name "Net-(J58-Pad4)") (class "Default")
      (node (ref "J58") (pin "4") (pinfunction "4_4") (pintype "passive"))
      (node (ref "J63") (pin "3") (pinfunction "3_3") (pintype "passive"))
    )
    (net (code "54") (name "Net-(J58-Pad6)") (class "Default")
      (node (ref "J58") (pin "6") (pinfunction "6_6") (pintype "passive"))
      (node (ref "J63") (pin "1") (pinfunction "1_1") (pintype "passive"))
    )
    (net (code "55") (name "Net-(J59-Pad1)") (class "Default")
      (node (ref "J59") (pin "1") (pinfunction "1_1") (pintype "passive"))
      (node (ref "J64") (pin "6") (pinfunction "6_6") (pintype "passive"))
    )
    (net (code "56") (name "Net-(J59-Pad2)") (class "Default")
      (node (ref "J59") (pin "2") (pinfunction "2_2") (pintype "passive"))
      (node (ref "J64") (pin "5") (pinfunction "5_5") (pintype "passive"))
    )
    (net (code "57") (name "Net-(J59-Pad3)") (class "Default")
      (node (ref "J59") (pin "3") (pinfunction "3_3") (pintype "passive"))
      (node (ref "J64") (pin "4") (pinfunction "4_4") (pintype "passive"))
    )
    (net (code "58") (name "Net-(J59-Pad4)") (class "Default")
      (node (ref "J59") (pin "4") (pinfunction "4_4") (pintype "passive"))
      (node (ref "J64") (pin "3") (pinfunction "3_3") (pintype "passive"))
    )
    (net (code "59") (name "Net-(J59-Pad6)") (class "Default")
      (node (ref "J59") (pin "6") (pinfunction "6_6") (pintype "passive"))
      (node (ref "J64") (pin "1") (pinfunction "1_1") (pintype "passive"))
    )
    (net (code "60") (name "Net-(J65-Pad1)") (class "Default")
      (node (ref "J65") (pin "1") (pinfunction "1_1") (pintype "passive"))
      (node (ref "J67") (pin "6") (pinfunction "6_6") (pintype "passive"))
    )
    (net (code "61") (name "Net-(J65-Pad2)") (class "Default")
      (node (ref "J65") (pin "2") (pinfunction "2_2") (pintype "passive"))
      (node (ref "J67") (pin "5") (pinfunction "5_5") (pintype "passive"))
    )
    (net (code "62") (name "Net-(J65-Pad3)") (class "Default")
      (node (ref "J65") (pin "3") (pinfunction "3_3") (pintype "passive"))
      (node (ref "J67") (pin "4") (pinfunction "4_4") (pintype "passive"))
    )
    (net (code "63") (name "Net-(J65-Pad4)") (class "Default")
      (node (ref "J65") (pin "4") (pinfunction "4_4") (pintype "passive"))
      (node (ref "J67") (pin "3") (pinfunction "3_3") (pintype "passive"))
    )
    (net (code "64") (name "Net-(J65-Pad6)") (class "Default")
      (node (ref "J65") (pin "6") (pinfunction "6_6") (pintype "passive"))
      (node (ref "J67") (pin "1") (pinfunction "1_1") (pintype "passive"))
    )
    (net (code "65") (name "Net-(J66-Pad1)") (class "Default")
      (node (ref "J66") (pin "1") (pinfunction "1_1") (pintype "passive"))
      (node (ref "J68") (pin "6") (pinfunction "6_6") (pintype "passive"))
    )
    (net (code "66") (name "Net-(J66-Pad2)") (class "Default")
      (node (ref "J66") (pin "2") (pinfunction "2_2") (pintype "passive"))
      (node (ref "J68") (pin "5") (pinfunction "5_5") (pintype "passive"))
    )
    (net (code "67") (name "Net-(J66-Pad3)") (class "Default")
      (node (ref "J66") (pin "3") (pinfunction "3_3") (pintype "passive"))
      (node (ref "J68") (pin "4") (pinfunction "4_4") (pintype "passive"))
    )
    (net (code "68") (name "Net-(J66-Pad4)") (class "Default")
      (node (ref "J66") (pin "4") (pinfunction "4_4") (pintype "passive"))
      (node (ref "J68") (pin "3") (pinfunction "3_3") (pintype "passive"))
    )
    (net (code "69") (name "Net-(J66-Pad6)") (class "Default")
      (node (ref "J66") (pin "6") (pinfunction "6_6") (pintype "passive"))
      (node (ref "J68") (pin "1") (pinfunction "1_1") (pintype "passive"))
    )
    (net (code "70") (name "unconnected-(J29-Pad1)") (class "Default")
      (node (ref "J29") (pin "1") (pinfunction "1_1") (pintype "passive+no_connect"))
    )
    (net (code "71") (name "unconnected-(J30-Pad1)") (class "Default")
      (node (ref "J30") (pin "1") (pinfunction "1_1") (pintype "passive+no_connect"))
    )
    (net (code "72") (name "unconnected-(J31-Pad1)") (class "Default")
      (node (ref "J31") (pin "1") (pinfunction "1_1") (pintype "passive+no_connect"))
    )
    (net (code "73") (name "unconnected-(J32-Pad1)") (class "Default")
      (node (ref "J32") (pin "1") (pinfunction "1_1") (pintype "passive+no_connect"))
    )
    (net (code "74") (name "unconnected-(J33-Pad1)") (class "Default")
      (node (ref "J33") (pin "1") (pinfunction "1_1") (pintype "passive+no_connect"))
    )
    (net (code "75") (name "unconnected-(J34-Pad1)") (class "Default")
      (node (ref "J34") (pin "1") (pinfunction "1_1") (pintype "passive+no_connect"))
    )
    (net (code "76") (name "unconnected-(J35-Pad1)") (class "Default")
      (node (ref "J35") (pin "1") (pinfunction "1_1") (pintype "passive+no_connect"))
    )
    (net (code "77") (name "unconnected-(J36-Pad1)") (class "Default")
      (node (ref "J36") (pin "1") (pinfunction "1_1") (pintype "passive+no_connect"))
    )
    (net (code "78") (name "unconnected-(J37-Pad1)") (class "Default")
      (node (ref "J37") (pin "1") (pinfunction "1_1") (pintype "passive+no_connect"))
    )
    (net (code "79") (name "unconnected-(J38-Pad1)") (class "Default")
      (node (ref "J38") (pin "1") (pinfunction "1_1") (pintype "passive+no_connect"))
    )
    (net (code "80") (name "unconnected-(J39-Pad1)") (class "Default")
      (node (ref "J39") (pin "1") (pinfunction "1_1") (pintype "passive+no_connect"))
    )
    (net (code "81") (name "unconnected-(J40-Pad1)") (class "Default")
      (node (ref "J40") (pin "1") (pinfunction "1_1") (pintype "passive+no_connect"))
    )
    (net (code "82") (name "unconnected-(J41-Pad1)") (class "Default")
      (node (ref "J41") (pin "1") (pinfunction "1_1") (pintype "passive+no_connect"))
    )
    (net (code "83") (name "unconnected-(J42-Pad1)") (class "Default")
      (node (ref "J42") (pin "1") (pinfunction "1_1") (pintype "passive+no_connect"))
    )
    (net (code "84") (name "unconnected-(J43-Pad1)") (class "Default")
      (node (ref "J43") (pin "1") (pinfunction "1_1") (pintype "passive+no_connect"))
    )
    (net (code "85") (name "unconnected-(J44-Pad1)") (class "Default")
      (node (ref "J44") (pin "1") (pinfunction "1_1") (pintype "passive+no_connect"))
    )
    (net (code "86") (name "unconnected-(J45-Pad1)") (class "Default")
      (node (ref "J45") (pin "1") (pinfunction "1_1") (pintype "passive+no_connect"))
    )
    (net (code "87") (name "unconnected-(J46-Pad1)") (class "Default")
      (node (ref "J46") (pin "1") (pinfunction "1_1") (pintype "passive+no_connect"))
    )
    (net (code "88") (name "unconnected-(J47-Pad1)") (class "Default")
      (node (ref "J47") (pin "1") (pinfunction "1_1") (pintype "passive+no_connect"))
    )
    (net (code "89") (name "unconnected-(J48-Pad1)") (class "Default")
      (node (ref "J48") (pin "1") (pinfunction "1_1") (pintype "passive+no_connect"))
    )
  )
)
